# ADE7753.net
KiCad netlist of a schematic drawn in Altium Designer
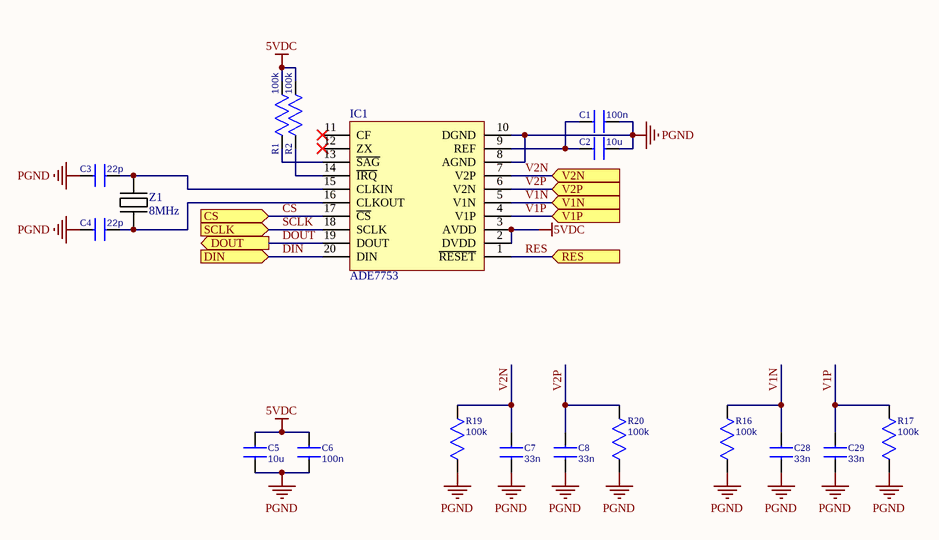
[diagram p0: ADE7753.SchDoc]

(export (version "E")
  (design (tool "Eeschema 10.0.6"))
  (components
    (comp (ref "C1")
      (value "100n")
      (footprint "C_0603")
      (description "Capacitor")
      (libsource (lib "AX_Altium_v2.3") (part "C0603"))
    )
    (comp (ref "C2")
      (value "10u")
      (footprint "C_0805")
      (description "Capacitor")
      (libsource (lib "AX_Altium_v2.3") (part "C0805"))
    )
    (comp (ref "C3")
      (value "22p")
      (footprint "C_0603")
      (description "Capacitor")
      (libsource (lib "AX_Altium_v2.3") (part "C0603"))
    )
    (comp (ref "C4")
      (value "22p")
      (footprint "C_0603")
      (description "Capacitor")
      (libsource (lib "AX_Altium_v2.3") (part "C0603"))
    )
    (comp (ref "C5")
      (value "10u")
      (footprint "C_0805")
      (description "Capacitor")
      (libsource (lib "AX_Altium_v2.3") (part "C0805"))
    )
    (comp (ref "C6")
      (value "100n")
      (footprint "C_0603")
      (description "Capacitor")
      (libsource (lib "AX_Altium_v2.3") (part "C0603"))
    )
    (comp (ref "C7")
      (value "33n")
      (footprint "C_0603")
      (description "Capacitor")
      (libsource (lib "AX_Altium_v2.3") (part "C0603"))
    )
    (comp (ref "C8")
      (value "33n")
      (footprint "C_0603")
      (description "Capacitor")
      (libsource (lib "AX_Altium_v2.3") (part "C0603"))
    )
    (comp (ref "C28")
      (value "33n")
      (footprint "C_0603")
      (description "Capacitor")
      (libsource (lib "AX_Altium_v2.3") (part "C0603"))
    )
    (comp (ref "C29")
      (value "33n")
      (footprint "C_0603")
      (description "Capacitor")
      (libsource (lib "AX_Altium_v2.3") (part "C0603"))
    )
    (comp (ref "IC1")
      (value "ADE7753")
      (footprint "SOP-20")
      (description "Data Acquisition ADC/DAC")
      (libsource (lib "SmartOutletIntegratedLibrary") (part "ADE7753ARSZ"))
    )
    (comp (ref "R1")
      (value "100k")
      (footprint "R_0603")
      (description "Resistor")
      (libsource (lib "AX_Altium_v2.3") (part "R0603"))
    )
    (comp (ref "R2")
      (value "100k")
      (footprint "R_0603")
      (description "Resistor")
      (libsource (lib "AX_Altium_v2.3") (part "R0603"))
    )
    (comp (ref "R16")
      (value "100k")
      (footprint "R_0603")
      (description "Resistor")
      (libsource (lib "AX_Altium_v2.3") (part "R0603"))
    )
    (comp (ref "R17")
      (value "100k")
      (footprint "R_0603")
      (description "Resistor")
      (libsource (lib "AX_Altium_v2.3") (part "R0603"))
    )
    (comp (ref "R19")
      (value "100k")
      (footprint "R_0603")
      (description "Resistor")
      (libsource (lib "AX_Altium_v2.3") (part "R0603"))
    )
    (comp (ref "R20")
      (value "100k")
      (footprint "R_0603")
      (description "Resistor")
      (libsource (lib "AX_Altium_v2.3") (part "R0603"))
    )
    (comp (ref "Z1")
      (value "8MHz")
      (footprint "HC-49")
      (description "Quartz resonator")
      (libsource (lib "Light_Music_Integrated_Library") (part "XTAL"))
    )
  )
  (nets
    (net (code "1") (name "/CS") (class "Default")
      (node (ref "IC1") (pin "17") (pinfunction "~{CS}_17") (pintype "passive"))
    )
    (net (code "2") (name "/DIN") (class "Default")
      (node (ref "IC1") (pin "20") (pinfunction "DIN_20") (pintype "passive"))
    )
    (net (code "3") (name "/DOUT") (class "Default")
      (node (ref "IC1") (pin "19") (pinfunction "DOUT_19") (pintype "passive"))
    )
    (net (code "4") (name "/RES") (class "Default")
      (node (ref "IC1") (pin "1") (pinfunction "~{RESET}_1") (pintype "passive"))
    )
    (net (code "5") (name "/SCLK") (class "Default")
      (node (ref "IC1") (pin "18") (pinfunction "SCLK_18") (pintype "passive"))
    )
    (net (code "6") (name "/V1N") (class "Default")
      (node (ref "C28") (pin "2") (pintype "passive"))
      (node (ref "IC1") (pin "5") (pinfunction "V1N_5") (pintype "passive"))
      (node (ref "R16") (pin "1") (pintype "passive"))
    )
    (net (code "7") (name "/V1P") (class "Default")
      (node (ref "C29") (pin "2") (pintype "passive"))
      (node (ref "IC1") (pin "4") (pinfunction "V1P_4") (pintype "passive"))
      (node (ref "R17") (pin "1") (pintype "passive"))
    )
    (net (code "8") (name "/V2N") (class "Default")
      (node (ref "C7") (pin "2") (pintype "passive"))
      (node (ref "IC1") (pin "7") (pinfunction "V2P_7") (pintype "passive"))
      (node (ref "R19") (pin "1") (pintype "passive"))
    )
    (net (code "9") (name "/V2P") (class "Default")
      (node (ref "C8") (pin "2") (pintype "passive"))
      (node (ref "IC1") (pin "6") (pinfunction "V2N_6") (pintype "passive"))
      (node (ref "R20") (pin "1") (pintype "passive"))
    )
    (net (code "10") (name "5VDC") (class "Default")
      (node (ref "C5") (pin "2") (pintype "passive"))
      (node (ref "C6") (pin "2") (pintype "passive"))
      (node (ref "IC1") (pin "2") (pinfunction "DVDD_2") (pintype "passive"))
      (node (ref "IC1") (pin "3") (pinfunction "AVDD_3") (pintype "passive"))
      (node (ref "R1") (pin "2") (pintype "passive"))
      (node (ref "R2") (pin "2") (pintype "passive"))
    )
    (net (code "11") (name "Net-(IC1-CLKIN)") (class "Default")
      (node (ref "C3") (pin "2") (pintype "passive"))
      (node (ref "IC1") (pin "15") (pinfunction "CLKIN_15") (pintype "passive"))
      (node (ref "Z1") (pin "2") (pinfunction "2_2") (pintype "passive"))
    )
    (net (code "12") (name "Net-(IC1-CLKOUT)") (class "Default")
      (node (ref "C4") (pin "2") (pintype "passive"))
      (node (ref "IC1") (pin "16") (pinfunction "CLKOUT_16") (pintype "passive"))
      (node (ref "Z1") (pin "1") (pinfunction "1_1") (pintype "passive"))
    )
    (net (code "13") (name "Net-(IC1-REF)") (class "Default")
      (node (ref "C1") (pin "1") (pintype "passive"))
      (node (ref "C2") (pin "1") (pintype "passive"))
      (node (ref "IC1") (pin "9") (pinfunction "REF_9") (pintype "passive"))
    )
    (net (code "14") (name "Net-(IC1-~{IRQ})") (class "Default")
      (node (ref "IC1") (pin "14") (pinfunction "~{IRQ}_14") (pintype "passive"))
      (node (ref "R2") (pin "1") (pintype "passive"))
    )
    (net (code "15") (name "Net-(IC1-~{SAG})") (class "Default")
      (node (ref "IC1") (pin "13") (pinfunction "~{SAG}_13") (pintype "passive"))
      (node (ref "R1") (pin "1") (pintype "passive"))
    )
    (net (code "16") (name "PGND") (class "Default")
      (node (ref "C1") (pin "2") (pintype "passive"))
      (node (ref "C2") (pin "2") (pintype "passive"))
      (node (ref "C28") (pin "1") (pintype "passive"))
      (node (ref "C29") (pin "1") (pintype "passive"))
      (node (ref "C3") (pin "1") (pintype "passive"))
      (node (ref "C4") (pin "1") (pintype "passive"))
      (node (ref "C5") (pin "1") (pintype "passive"))
      (node (ref "C6") (pin "1") (pintype "passive"))
      (node (ref "C7") (pin "1") (pintype "passive"))
      (node (ref "C8") (pin "1") (pintype "passive"))
      (node (ref "IC1") (pin "10") (pinfunction "DGND_10") (pintype "passive"))
      (node (ref "IC1") (pin "8") (pinfunction "AGND_8") (pintype "passive"))
      (node (ref "R16") (pin "2") (pintype "passive"))
      (node (ref "R17") (pin "2") (pintype "passive"))
      (node (ref "R19") (pin "2") (pintype "passive"))
      (node (ref "R20") (pin "2") (pintype "passive"))
    )
    (net (code "17") (name "unconnected-(IC1-CF-Pad11)") (class "Default")
      (node (ref "IC1") (pin "11") (pinfunction "CF_11") (pintype "passive+no_connect"))
    )
    (net (code "18") (name "unconnected-(IC1-ZX-Pad12)") (class "Default")
      (node (ref "IC1") (pin "12") (pinfunction "ZX_12") (pintype "passive+no_connect"))
    )
  )
)
